# CampLet_Power_Control.net
KiCad netlist of a schematic drawn in EAGLE
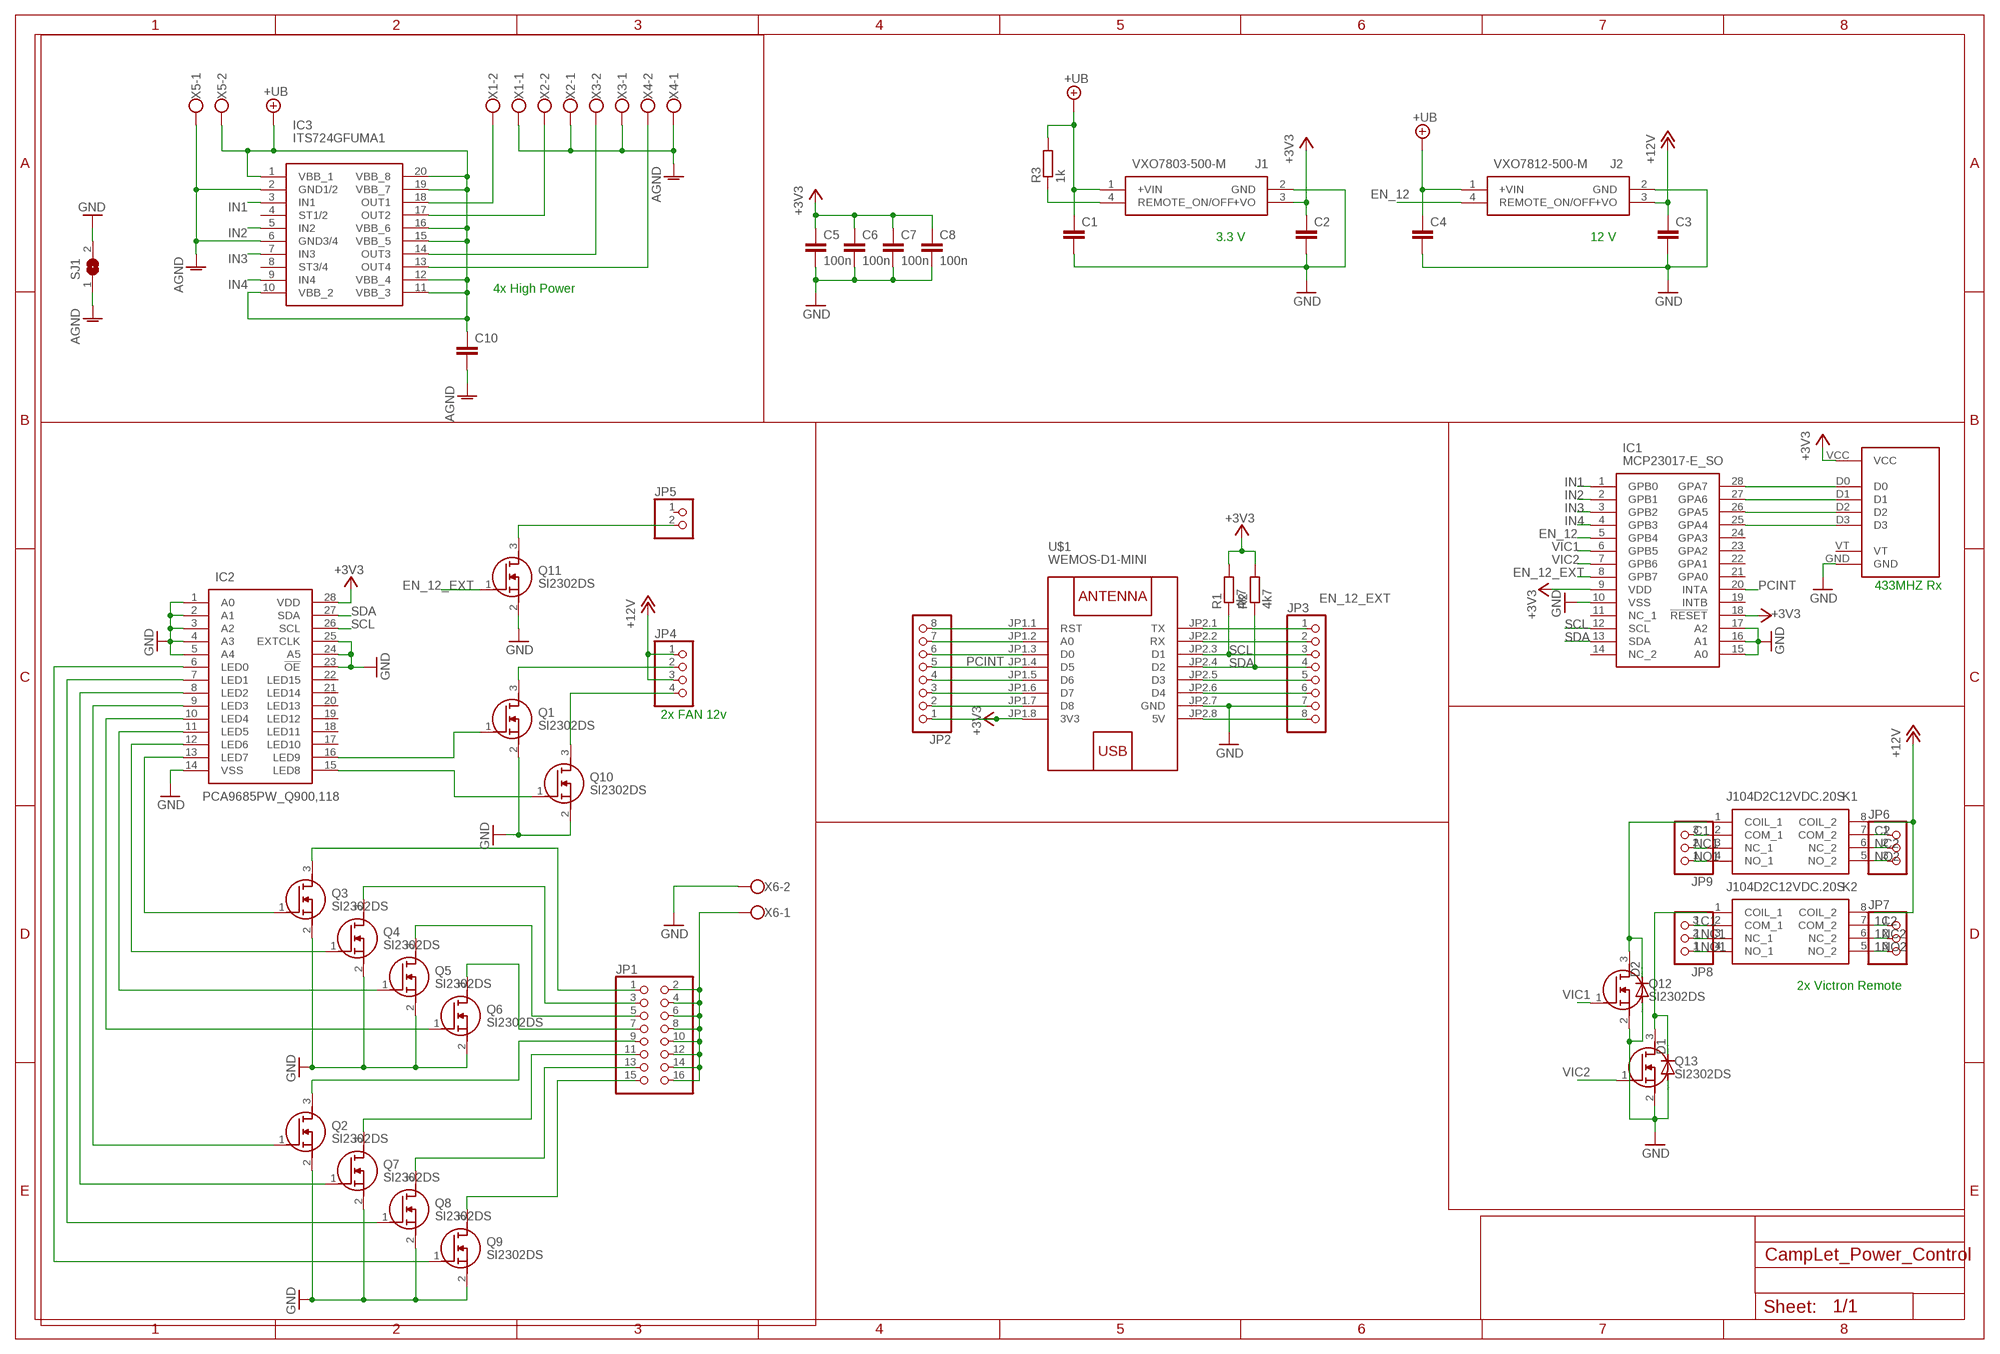
[diagram p0: schematic, sheet 1]

(export (version "E")
  (design (tool "Eeschema 10.0.6"))
  (components
    (comp (ref "C1")
      (value "10u 30v CL31A106KBHNNNE")
      (footprint "eagle-import:C1206")
      (libsource (lib "eagle-import") (part "C-EUC1206"))
    )
    (comp (ref "C2")
      (value "22u 3.3v CL31A226MOCLNNC")
      (footprint "eagle-import:C1206")
      (libsource (lib "eagle-import") (part "C-EUC1206"))
    )
    (comp (ref "C3")
      (value "22u 12v CL31A226MOCLNNC")
      (footprint "eagle-import:C1206")
      (libsource (lib "eagle-import") (part "C-EUC1206"))
    )
    (comp (ref "C4")
      (value "10u 30v CL31A106KBHNNNE")
      (footprint "eagle-import:C1206")
      (libsource (lib "eagle-import") (part "C-EUC1206"))
    )
    (comp (ref "C5")
      (value "100n")
      (footprint "eagle-import:C0805")
      (libsource (lib "eagle-import") (part "C-EUC0805"))
    )
    (comp (ref "C6")
      (value "100n")
      (footprint "eagle-import:C0805")
      (libsource (lib "eagle-import") (part "C-EUC0805"))
    )
    (comp (ref "C7")
      (value "100n")
      (footprint "eagle-import:C0805")
      (libsource (lib "eagle-import") (part "C-EUC0805"))
    )
    (comp (ref "C8")
      (value "100n")
      (footprint "eagle-import:C0805")
      (libsource (lib "eagle-import") (part "C-EUC0805"))
    )
    (comp (ref "C10")
      (value "10u 30v CL31A106KBHNNNE")
      (footprint "eagle-import:C1206")
      (libsource (lib "eagle-import") (part "C-EUC1206"))
    )
    (comp (ref "D1")
      (value "1N4148DO35-7")
      (footprint "eagle-import:DO35-7")
      (libsource (lib "eagle-import") (part "1N4148DO35-7"))
    )
    (comp (ref "D2")
      (value "1N4148DO35-7")
      (footprint "eagle-import:DO35-7")
      (libsource (lib "eagle-import") (part "1N4148DO35-7"))
    )
    (comp (ref "IC1")
      (value "MCP23017-E_SO")
      (footprint "eagle-import:SOIC127P1030X265-28N")
      (fields
        (field (name "ARROW_PART_NUMBER") "MCP23017-E/SO")
        (field (name "MOUSER_PART_NUMBER") "579-MCP23017-E/SO")
      )
      (libsource (lib "eagle-import") (part "MCP23017-E_SO"))
    )
    (comp (ref "IC2")
      (value "PCA9685PW_Q900,118")
      (footprint "eagle-import:SOP65P640X110-28N")
      (fields
        (field (name "ARROW_PART_NUMBER") "PCA9685PW/Q900,118")
        (field (name "MOUSER_PART_NUMBER") "771-PCA9685PWQ900118")
      )
      (libsource (lib "eagle-import") (part "PCA9685PW_Q900,118"))
    )
    (comp (ref "IC3")
      (value "ITS724GFUMA1")
      (footprint "eagle-import:SOIC127P1030X265-20N")
      (fields (field (name "MOUSER_PART_NUMBER") "726-ITS724GFUMA1"))
      (libsource (lib "eagle-import") (part "ITS724GFUMA1"))
    )
    (comp (ref "J1")
      (value "VXO7803-500-M")
      (footprint "eagle-import:VXO7803500MTR")
      (fields
        (field (name "ARROW_PART_NUMBER") "VXO7803-500-M-TR")
        (field (name "MOUSER_PART_NUMBER") "490-VXO7803-500-M-TR")
      )
      (libsource (lib "eagle-import") (part "VXO7803-500-M-TR"))
    )
    (comp (ref "J2")
      (value "VXO7812-500-M")
      (footprint "eagle-import:VXO7803500MTR")
      (fields
        (field (name "ARROW_PART_NUMBER") "VXO7803-500-M-TR")
        (field (name "MOUSER_PART_NUMBER") "490-VXO7803-500-M-TR")
      )
      (libsource (lib "eagle-import") (part "VXO7803-500-M-TR"))
    )
    (comp (ref "JP1")
      (value "PINHD-2X8")
      (footprint "eagle-import:2X08")
      (libsource (lib "eagle-import") (part "PINHD-2X8"))
    )
    (comp (ref "JP2")
      (value "PINHD-1X8")
      (footprint "eagle-import:1X08")
      (libsource (lib "eagle-import") (part "PINHD-1X8"))
    )
    (comp (ref "JP3")
      (value "PINHD-1X8")
      (footprint "eagle-import:1X08")
      (libsource (lib "eagle-import") (part "PINHD-1X8"))
    )
    (comp (ref "JP4")
      (value "PINHD-1X4")
      (footprint "eagle-import:1X04")
      (libsource (lib "eagle-import") (part "PINHD-1X4"))
    )
    (comp (ref "JP5")
      (value "PINHD-1X2")
      (footprint "eagle-import:1X02")
      (libsource (lib "eagle-import") (part "PINHD-1X2"))
    )
    (comp (ref "JP6")
      (value "PINHD-1X3")
      (footprint "eagle-import:1X03")
      (libsource (lib "eagle-import") (part "PINHD-1X3"))
    )
    (comp (ref "JP7")
      (value "PINHD-1X3")
      (footprint "eagle-import:1X03")
      (libsource (lib "eagle-import") (part "PINHD-1X3"))
    )
    (comp (ref "JP8")
      (value "PINHD-1X3")
      (footprint "eagle-import:1X03")
      (libsource (lib "eagle-import") (part "PINHD-1X3"))
    )
    (comp (ref "JP9")
      (value "PINHD-1X3")
      (footprint "eagle-import:1X03")
      (libsource (lib "eagle-import") (part "PINHD-1X3"))
    )
    (comp (ref "K1")
      (value "J104D2C12VDC.20S")
      (footprint "eagle-import:J104D2C12VDC20S")
      (libsource (lib "eagle-import") (part "J104D2C12VDC.20S"))
    )
    (comp (ref "K2")
      (value "J104D2C12VDC.20S")
      (footprint "eagle-import:J104D2C12VDC20S")
      (libsource (lib "eagle-import") (part "J104D2C12VDC.20S"))
    )
    (comp (ref "Q1")
      (value "SI2302DS")
      (footprint "eagle-import:SOT95P230X110-3N")
      (libsource (lib "eagle-import") (part "SI2302DS"))
    )
    (comp (ref "Q2")
      (value "SI2302DS")
      (footprint "eagle-import:SOT95P230X110-3N")
      (libsource (lib "eagle-import") (part "SI2302DS"))
    )
    (comp (ref "Q3")
      (value "SI2302DS")
      (footprint "eagle-import:SOT95P230X110-3N")
      (libsource (lib "eagle-import") (part "SI2302DS"))
    )
    (comp (ref "Q4")
      (value "SI2302DS")
      (footprint "eagle-import:SOT95P230X110-3N")
      (libsource (lib "eagle-import") (part "SI2302DS"))
    )
    (comp (ref "Q5")
      (value "SI2302DS")
      (footprint "eagle-import:SOT95P230X110-3N")
      (libsource (lib "eagle-import") (part "SI2302DS"))
    )
    (comp (ref "Q6")
      (value "SI2302DS")
      (footprint "eagle-import:SOT95P230X110-3N")
      (libsource (lib "eagle-import") (part "SI2302DS"))
    )
    (comp (ref "Q7")
      (value "SI2302DS")
      (footprint "eagle-import:SOT95P230X110-3N")
      (libsource (lib "eagle-import") (part "SI2302DS"))
    )
    (comp (ref "Q8")
      (value "SI2302DS")
      (footprint "eagle-import:SOT95P230X110-3N")
      (libsource (lib "eagle-import") (part "SI2302DS"))
    )
    (comp (ref "Q9")
      (value "SI2302DS")
      (footprint "eagle-import:SOT95P230X110-3N")
      (libsource (lib "eagle-import") (part "SI2302DS"))
    )
    (comp (ref "Q10")
      (value "SI2302DS")
      (footprint "eagle-import:SOT95P230X110-3N")
      (libsource (lib "eagle-import") (part "SI2302DS"))
    )
    (comp (ref "Q11")
      (value "SI2302DS")
      (footprint "eagle-import:SOT95P230X110-3N")
      (libsource (lib "eagle-import") (part "SI2302DS"))
    )
    (comp (ref "Q12")
      (value "SI2302DS")
      (footprint "eagle-import:SOT95P230X110-3N")
      (libsource (lib "eagle-import") (part "SI2302DS"))
    )
    (comp (ref "Q13")
      (value "SI2302DS")
      (footprint "eagle-import:SOT95P230X110-3N")
      (libsource (lib "eagle-import") (part "SI2302DS"))
    )
    (comp (ref "R1")
      (value "4k7")
      (footprint "eagle-import:R0805")
      (libsource (lib "eagle-import") (part "R-EU_R0805"))
    )
    (comp (ref "R2")
      (value "4k7")
      (footprint "eagle-import:R0805")
      (libsource (lib "eagle-import") (part "R-EU_R0805"))
    )
    (comp (ref "R3")
      (value "1k")
      (footprint "eagle-import:R0805")
      (libsource (lib "eagle-import") (part "R-EU_R0805"))
    )
    (comp (ref "SJ1") (value "SJ") (footprint "eagle-import:SJ") (libsource (lib "eagle-import") (part "SJ")))
    (comp (ref "U$1")
      (value "WEMOS-D1-MINI")
      (footprint "eagle-import:WEMOS-D1-MINI")
      (libsource (lib "eagle-import") (part "WEMOS-D1-MINI"))
    )
    (comp (ref "U$2")
      (value "433MHZ")
      (footprint "eagle-import:433MHZ")
      (libsource (lib "eagle-import") (part "433MHZ"))
    )
    (comp (ref "X1")
      (value "W237-102")
      (footprint "eagle-import:W237-102")
      (fields (field (name "MPN") "237-102"))
      (libsource (lib "eagle-import") (part "W237-102"))
    )
    (comp (ref "X2")
      (value "W237-102")
      (footprint "eagle-import:W237-102")
      (fields (field (name "MPN") "237-102"))
      (libsource (lib "eagle-import") (part "W237-102"))
    )
    (comp (ref "X3")
      (value "W237-102")
      (footprint "eagle-import:W237-102")
      (fields (field (name "MPN") "237-102"))
      (libsource (lib "eagle-import") (part "W237-102"))
    )
    (comp (ref "X4")
      (value "W237-102")
      (footprint "eagle-import:W237-102")
      (fields (field (name "MPN") "237-102"))
      (libsource (lib "eagle-import") (part "W237-102"))
    )
    (comp (ref "X5")
      (value "W237-102")
      (footprint "eagle-import:W237-102")
      (fields (field (name "MPN") "237-102"))
      (libsource (lib "eagle-import") (part "W237-102"))
    )
    (comp (ref "X6")
      (value "W237-102")
      (footprint "eagle-import:W237-102")
      (fields (field (name "MPN") "237-102"))
      (libsource (lib "eagle-import") (part "W237-102"))
    )
  )
  (nets
    (net (code "1") (name "+3V3") (class "Default")
      (node (ref "C2") (pin "1") (pinfunction "1_1") (pintype "passive"))
      (node (ref "C5") (pin "1") (pinfunction "1_1") (pintype "passive"))
      (node (ref "C6") (pin "1") (pinfunction "1_1") (pintype "passive"))
      (node (ref "C7") (pin "1") (pinfunction "1_1") (pintype "passive"))
      (node (ref "C8") (pin "1") (pinfunction "1_1") (pintype "passive"))
      (node (ref "IC1") (pin "18") (pinfunction "~{RESET}_18") (pintype "bidirectional"))
      (node (ref "IC1") (pin "9") (pinfunction "VDD_9") (pintype "bidirectional"))
      (node (ref "IC2") (pin "28") (pinfunction "VDD_28") (pintype "bidirectional"))
      (node (ref "J1") (pin "3") (pinfunction "+VO_3") (pintype "bidirectional"))
      (node (ref "JP2") (pin "1") (pinfunction "1_1") (pintype "passive"))
      (node (ref "R1") (pin "2") (pinfunction "2_2") (pintype "passive"))
      (node (ref "R2") (pin "2") (pinfunction "2_2") (pintype "passive"))
      (node (ref "U$1") (pin "JP1.8") (pinfunction "3V3_JP1.8") (pintype "power_in"))
      (node (ref "U$2") (pin "VCC") (pinfunction "VCC_VCC") (pintype "bidirectional"))
    )
    (net (code "2") (name "+12V") (class "Default")
      (node (ref "C3") (pin "1") (pinfunction "1_1") (pintype "passive"))
      (node (ref "J2") (pin "3") (pinfunction "+VO_3") (pintype "bidirectional"))
      (node (ref "JP4") (pin "1") (pinfunction "1_1") (pintype "passive"))
      (node (ref "JP4") (pin "3") (pinfunction "3_3") (pintype "passive"))
      (node (ref "K1") (pin "8") (pinfunction "COIL_2_8") (pintype "bidirectional"))
      (node (ref "K2") (pin "8") (pinfunction "COIL_2_8") (pintype "bidirectional"))
    )
    (net (code "3") (name "+UB") (class "Default")
      (node (ref "C1") (pin "1") (pinfunction "1_1") (pintype "passive"))
      (node (ref "C10") (pin "1") (pinfunction "1_1") (pintype "passive"))
      (node (ref "C4") (pin "1") (pinfunction "1_1") (pintype "passive"))
      (node (ref "IC3") (pin "1") (pinfunction "VBB_1_1") (pintype "bidirectional"))
      (node (ref "IC3") (pin "10") (pinfunction "VBB_2_10") (pintype "bidirectional"))
      (node (ref "IC3") (pin "11") (pinfunction "VBB_3_11") (pintype "bidirectional"))
      (node (ref "IC3") (pin "12") (pinfunction "VBB_4_12") (pintype "bidirectional"))
      (node (ref "IC3") (pin "15") (pinfunction "VBB_5_15") (pintype "bidirectional"))
      (node (ref "IC3") (pin "16") (pinfunction "VBB_6_16") (pintype "bidirectional"))
      (node (ref "IC3") (pin "19") (pinfunction "VBB_7_19") (pintype "bidirectional"))
      (node (ref "IC3") (pin "20") (pinfunction "VBB_8_20") (pintype "bidirectional"))
      (node (ref "J1") (pin "1") (pinfunction "+VIN_1") (pintype "bidirectional"))
      (node (ref "J2") (pin "1") (pinfunction "+VIN_1") (pintype "bidirectional"))
      (node (ref "R3") (pin "2") (pinfunction "2_2") (pintype "passive"))
      (node (ref "X5") (pin "2") (pinfunction "KL_2") (pintype "passive"))
    )
    (net (code "4") (name "/1C1") (class "Default")
      (node (ref "JP8") (pin "3") (pinfunction "3_3") (pintype "passive"))
      (node (ref "K2") (pin "2") (pinfunction "COM_1_2") (pintype "bidirectional"))
    )
    (net (code "5") (name "/1C2") (class "Default")
      (node (ref "JP7") (pin "1") (pinfunction "1_1") (pintype "passive"))
      (node (ref "K2") (pin "7") (pinfunction "COM_2_7") (pintype "bidirectional"))
    )
    (net (code "6") (name "/1NC1") (class "Default")
      (node (ref "JP8") (pin "2") (pinfunction "2_2") (pintype "passive"))
      (node (ref "K2") (pin "3") (pinfunction "NC_1_3") (pintype "bidirectional"))
    )
    (net (code "7") (name "/1NC2") (class "Default")
      (node (ref "JP7") (pin "2") (pinfunction "2_2") (pintype "passive"))
      (node (ref "K2") (pin "6") (pinfunction "NC_2_6") (pintype "bidirectional"))
    )
    (net (code "8") (name "/1NO1") (class "Default")
      (node (ref "JP8") (pin "1") (pinfunction "1_1") (pintype "passive"))
      (node (ref "K2") (pin "4") (pinfunction "NO_1_4") (pintype "bidirectional"))
    )
    (net (code "9") (name "/1NO2") (class "Default")
      (node (ref "JP7") (pin "3") (pinfunction "3_3") (pintype "passive"))
      (node (ref "K2") (pin "5") (pinfunction "NO_2_5") (pintype "bidirectional"))
    )
    (net (code "10") (name "/C1") (class "Default")
      (node (ref "JP9") (pin "3") (pinfunction "3_3") (pintype "passive"))
      (node (ref "K1") (pin "2") (pinfunction "COM_1_2") (pintype "bidirectional"))
    )
    (net (code "11") (name "/C2") (class "Default")
      (node (ref "JP6") (pin "1") (pinfunction "1_1") (pintype "passive"))
      (node (ref "K1") (pin "7") (pinfunction "COM_2_7") (pintype "bidirectional"))
    )
    (net (code "12") (name "/EN_12") (class "Default")
      (node (ref "IC1") (pin "5") (pinfunction "GPB4_5") (pintype "bidirectional"))
      (node (ref "J2") (pin "4") (pinfunction "REMOTE_ON/OFF_4") (pintype "bidirectional"))
    )
    (net (code "13") (name "/EN_12_EXT") (class "Default")
      (node (ref "IC1") (pin "8") (pinfunction "GPB7_8") (pintype "bidirectional"))
      (node (ref "Q11") (pin "1") (pinfunction "G_1") (pintype "bidirectional"))
    )
    (net (code "14") (name "/IN1") (class "Default")
      (node (ref "IC1") (pin "1") (pinfunction "GPB0_1") (pintype "bidirectional"))
      (node (ref "IC3") (pin "3") (pinfunction "IN1_3") (pintype "bidirectional"))
    )
    (net (code "15") (name "/IN2") (class "Default")
      (node (ref "IC1") (pin "2") (pinfunction "GPB1_2") (pintype "bidirectional"))
      (node (ref "IC3") (pin "5") (pinfunction "IN2_5") (pintype "bidirectional"))
    )
    (net (code "16") (name "/IN3") (class "Default")
      (node (ref "IC1") (pin "3") (pinfunction "GPB2_3") (pintype "bidirectional"))
      (node (ref "IC3") (pin "7") (pinfunction "IN3_7") (pintype "bidirectional"))
    )
    (net (code "17") (name "/IN4") (class "Default")
      (node (ref "IC1") (pin "4") (pinfunction "GPB3_4") (pintype "bidirectional"))
      (node (ref "IC3") (pin "9") (pinfunction "IN4_9") (pintype "bidirectional"))
    )
    (net (code "18") (name "/NC1") (class "Default")
      (node (ref "JP9") (pin "2") (pinfunction "2_2") (pintype "passive"))
      (node (ref "K1") (pin "3") (pinfunction "NC_1_3") (pintype "bidirectional"))
    )
    (net (code "19") (name "/NC2") (class "Default")
      (node (ref "JP6") (pin "2") (pinfunction "2_2") (pintype "passive"))
      (node (ref "K1") (pin "6") (pinfunction "NC_2_6") (pintype "bidirectional"))
    )
    (net (code "20") (name "/NO1") (class "Default")
      (node (ref "JP9") (pin "1") (pinfunction "1_1") (pintype "passive"))
      (node (ref "K1") (pin "4") (pinfunction "NO_1_4") (pintype "bidirectional"))
    )
    (net (code "21") (name "/NO2") (class "Default")
      (node (ref "JP6") (pin "3") (pinfunction "3_3") (pintype "passive"))
      (node (ref "K1") (pin "5") (pinfunction "NO_2_5") (pintype "bidirectional"))
    )
    (net (code "22") (name "/PCINT") (class "Default")
      (node (ref "IC1") (pin "20") (pinfunction "INTA_20") (pintype "bidirectional"))
      (node (ref "JP2") (pin "5") (pinfunction "5_5") (pintype "passive"))
      (node (ref "U$1") (pin "JP1.4") (pinfunction "D5_JP1.4") (pintype "bidirectional"))
    )
    (net (code "23") (name "/SCL") (class "Default")
      (node (ref "IC1") (pin "12") (pinfunction "SCL_12") (pintype "bidirectional"))
      (node (ref "IC2") (pin "26") (pinfunction "SCL_26") (pintype "bidirectional"))
      (node (ref "JP3") (pin "3") (pinfunction "3_3") (pintype "passive"))
      (node (ref "R1") (pin "1") (pinfunction "1_1") (pintype "passive"))
      (node (ref "U$1") (pin "JP2.3") (pinfunction "D1_JP2.3") (pintype "bidirectional"))
    )
    (net (code "24") (name "/SDA") (class "Default")
      (node (ref "IC1") (pin "13") (pinfunction "SDA_13") (pintype "bidirectional"))
      (node (ref "IC2") (pin "27") (pinfunction "SDA_27") (pintype "bidirectional"))
      (node (ref "JP3") (pin "4") (pinfunction "4_4") (pintype "passive"))
      (node (ref "R2") (pin "1") (pinfunction "1_1") (pintype "passive"))
      (node (ref "U$1") (pin "JP2.4") (pinfunction "D2_JP2.4") (pintype "bidirectional"))
    )
    (net (code "25") (name "/VIC1") (class "Default")
      (node (ref "IC1") (pin "6") (pinfunction "GPB5_6") (pintype "bidirectional"))
      (node (ref "Q12") (pin "1") (pinfunction "G_1") (pintype "bidirectional"))
    )
    (net (code "26") (name "/VIC2") (class "Default")
      (node (ref "IC1") (pin "7") (pinfunction "GPB6_7") (pintype "bidirectional"))
      (node (ref "Q13") (pin "1") (pinfunction "G_1") (pintype "bidirectional"))
    )
    (net (code "27") (name "AGND") (class "Default")
      (node (ref "C10") (pin "2") (pinfunction "2_2") (pintype "passive"))
      (node (ref "IC3") (pin "2") (pinfunction "GND1/2_2") (pintype "bidirectional"))
      (node (ref "IC3") (pin "6") (pinfunction "GND3/4_6") (pintype "bidirectional"))
      (node (ref "SJ1") (pin "1") (pinfunction "1_1") (pintype "passive"))
      (node (ref "X1") (pin "1") (pinfunction "KL_1") (pintype "passive"))
      (node (ref "X2") (pin "1") (pinfunction "KL_1") (pintype "passive"))
      (node (ref "X3") (pin "1") (pinfunction "KL_1") (pintype "passive"))
      (node (ref "X4") (pin "1") (pinfunction "KL_1") (pintype "passive"))
      (node (ref "X5") (pin "1") (pinfunction "KL_1") (pintype "passive"))
    )
    (net (code "28") (name "GND") (class "Default")
      (node (ref "C1") (pin "2") (pinfunction "2_2") (pintype "passive"))
      (node (ref "C2") (pin "2") (pinfunction "2_2") (pintype "passive"))
      (node (ref "C3") (pin "2") (pinfunction "2_2") (pintype "passive"))
      (node (ref "C4") (pin "2") (pinfunction "2_2") (pintype "passive"))
      (node (ref "C5") (pin "2") (pinfunction "2_2") (pintype "passive"))
      (node (ref "C6") (pin "2") (pinfunction "2_2") (pintype "passive"))
      (node (ref "C7") (pin "2") (pinfunction "2_2") (pintype "passive"))
      (node (ref "C8") (pin "2") (pinfunction "2_2") (pintype "passive"))
      (node (ref "D1") (pin "A") (pinfunction "A_A") (pintype "passive"))
      (node (ref "D2") (pin "A") (pinfunction "A_A") (pintype "passive"))
      (node (ref "IC1") (pin "10") (pinfunction "VSS_10") (pintype "bidirectional"))
      (node (ref "IC1") (pin "15") (pinfunction "A0_15") (pintype "bidirectional"))
      (node (ref "IC1") (pin "16") (pinfunction "A1_16") (pintype "bidirectional"))
      (node (ref "IC1") (pin "17") (pinfunction "A2_17") (pintype "bidirectional"))
      (node (ref "IC2") (pin "1") (pinfunction "A0_1") (pintype "bidirectional"))
      (node (ref "IC2") (pin "14") (pinfunction "VSS_14") (pintype "bidirectional"))
      (node (ref "IC2") (pin "2") (pinfunction "A1_2") (pintype "bidirectional"))
      (node (ref "IC2") (pin "23") (pinfunction "~{OE}_23") (pintype "bidirectional"))
      (node (ref "IC2") (pin "24") (pinfunction "A5_24") (pintype "bidirectional"))
      (node (ref "IC2") (pin "25") (pinfunction "EXTCLK_25") (pintype "bidirectional"))
      (node (ref "IC2") (pin "3") (pinfunction "A2_3") (pintype "bidirectional"))
      (node (ref "IC2") (pin "4") (pinfunction "A3_4") (pintype "bidirectional"))
      (node (ref "IC2") (pin "5") (pinfunction "A4_5") (pintype "bidirectional"))
      (node (ref "J1") (pin "2") (pinfunction "GND_2") (pintype "bidirectional"))
      (node (ref "J2") (pin "2") (pinfunction "GND_2") (pintype "bidirectional"))
      (node (ref "JP3") (pin "7") (pinfunction "7_7") (pintype "passive"))
      (node (ref "Q1") (pin "2") (pinfunction "S_2") (pintype "bidirectional"))
      (node (ref "Q10") (pin "2") (pinfunction "S_2") (pintype "bidirectional"))
      (node (ref "Q11") (pin "2") (pinfunction "S_2") (pintype "bidirectional"))
      (node (ref "Q12") (pin "2") (pinfunction "S_2") (pintype "bidirectional"))
      (node (ref "Q13") (pin "2") (pinfunction "S_2") (pintype "bidirectional"))
      (node (ref "Q2") (pin "2") (pinfunction "S_2") (pintype "bidirectional"))
      (node (ref "Q3") (pin "2") (pinfunction "S_2") (pintype "bidirectional"))
      (node (ref "Q4") (pin "2") (pinfunction "S_2") (pintype "bidirectional"))
      (node (ref "Q5") (pin "2") (pinfunction "S_2") (pintype "bidirectional"))
      (node (ref "Q6") (pin "2") (pinfunction "S_2") (pintype "bidirectional"))
      (node (ref "Q7") (pin "2") (pinfunction "S_2") (pintype "bidirectional"))
      (node (ref "Q8") (pin "2") (pinfunction "S_2") (pintype "bidirectional"))
      (node (ref "Q9") (pin "2") (pinfunction "S_2") (pintype "bidirectional"))
      (node (ref "SJ1") (pin "2") (pinfunction "2_2") (pintype "passive"))
      (node (ref "U$1") (pin "JP2.7") (pinfunction "GND_JP2.7") (pintype "power_in"))
      (node (ref "U$2") (pin "GND") (pinfunction "GND_GND") (pintype "bidirectional"))
      (node (ref "X6") (pin "2") (pinfunction "KL_2") (pintype "passive"))
    )
    (net (code "29") (name "Net-(IC1-GPA4)") (class "Default")
      (node (ref "IC1") (pin "25") (pinfunction "GPA4_25") (pintype "bidirectional"))
      (node (ref "U$2") (pin "D3") (pinfunction "D3_D3") (pintype "bidirectional"))
    )
    (net (code "30") (name "Net-(IC1-GPA5)") (class "Default")
      (node (ref "IC1") (pin "26") (pinfunction "GPA5_26") (pintype "bidirectional"))
      (node (ref "U$2") (pin "D2") (pinfunction "D2_D2") (pintype "bidirectional"))
    )
    (net (code "31") (name "Net-(IC1-GPA6)") (class "Default")
      (node (ref "IC1") (pin "27") (pinfunction "GPA6_27") (pintype "bidirectional"))
      (node (ref "U$2") (pin "D1") (pinfunction "D1_D1") (pintype "bidirectional"))
    )
    (net (code "32") (name "Net-(IC1-GPA7)") (class "Default")
      (node (ref "IC1") (pin "28") (pinfunction "GPA7_28") (pintype "bidirectional"))
      (node (ref "U$2") (pin "D0") (pinfunction "D0_D0") (pintype "bidirectional"))
    )
    (net (code "33") (name "Net-(IC2-LED0)") (class "Default")
      (node (ref "IC2") (pin "6") (pinfunction "LED0_6") (pintype "bidirectional"))
      (node (ref "Q9") (pin "1") (pinfunction "G_1") (pintype "bidirectional"))
    )
    (net (code "34") (name "Net-(IC2-LED1)") (class "Default")
      (node (ref "IC2") (pin "7") (pinfunction "LED1_7") (pintype "bidirectional"))
      (node (ref "Q8") (pin "1") (pinfunction "G_1") (pintype "bidirectional"))
    )
    (net (code "35") (name "Net-(IC2-LED2)") (class "Default")
      (node (ref "IC2") (pin "8") (pinfunction "LED2_8") (pintype "bidirectional"))
      (node (ref "Q7") (pin "1") (pinfunction "G_1") (pintype "bidirectional"))
    )
    (net (code "36") (name "Net-(IC2-LED3)") (class "Default")
      (node (ref "IC2") (pin "9") (pinfunction "LED3_9") (pintype "bidirectional"))
      (node (ref "Q2") (pin "1") (pinfunction "G_1") (pintype "bidirectional"))
    )
    (net (code "37") (name "Net-(IC2-LED4)") (class "Default")
      (node (ref "IC2") (pin "10") (pinfunction "LED4_10") (pintype "bidirectional"))
      (node (ref "Q6") (pin "1") (pinfunction "G_1") (pintype "bidirectional"))
    )
    (net (code "38") (name "Net-(IC2-LED5)") (class "Default")
      (node (ref "IC2") (pin "11") (pinfunction "LED5_11") (pintype "bidirectional"))
      (node (ref "Q5") (pin "1") (pinfunction "G_1") (pintype "bidirectional"))
    )
    (net (code "39") (name "Net-(IC2-LED6)") (class "Default")
      (node (ref "IC2") (pin "12") (pinfunction "LED6_12") (pintype "bidirectional"))
      (node (ref "Q4") (pin "1") (pinfunction "G_1") (pintype "bidirectional"))
    )
    (net (code "40") (name "Net-(IC2-LED7)") (class "Default")
      (node (ref "IC2") (pin "13") (pinfunction "LED7_13") (pintype "bidirectional"))
      (node (ref "Q3") (pin "1") (pinfunction "G_1") (pintype "bidirectional"))
    )
    (net (code "41") (name "Net-(IC2-LED8)") (class "Default")
      (node (ref "IC2") (pin "15") (pinfunction "LED8_15") (pintype "bidirectional"))
      (node (ref "Q10") (pin "1") (pinfunction "G_1") (pintype "bidirectional"))
    )
    (net (code "42") (name "Net-(IC2-LED9)") (class "Default")
      (node (ref "IC2") (pin "16") (pinfunction "LED9_16") (pintype "bidirectional"))
      (node (ref "Q1") (pin "1") (pinfunction "G_1") (pintype "bidirectional"))
    )
    (net (code "43") (name "Net-(IC3-OUT1)") (class "Default")
      (node (ref "IC3") (pin "18") (pinfunction "OUT1_18") (pintype "bidirectional"))
      (node (ref "X1") (pin "2") (pinfunction "KL_2") (pintype "passive"))
    )
    (net (code "44") (name "Net-(IC3-OUT2)") (class "Default")
      (node (ref "IC3") (pin "17") (pinfunction "OUT2_17") (pintype "bidirectional"))
      (node (ref "X2") (pin "2") (pinfunction "KL_2") (pintype "passive"))
    )
    (net (code "45") (name "Net-(IC3-OUT3)") (class "Default")
      (node (ref "IC3") (pin "14") (pinfunction "OUT3_14") (pintype "bidirectional"))
      (node (ref "X3") (pin "2") (pinfunction "KL_2") (pintype "passive"))
    )
    (net (code "46") (name "Net-(IC3-OUT4)") (class "Default")
      (node (ref "IC3") (pin "13") (pinfunction "OUT4_13") (pintype "bidirectional"))
      (node (ref "X4") (pin "2") (pinfunction "KL_2") (pintype "passive"))
    )
    (net (code "47") (name "Net-(J1-REMOTE_ON{slash}OFF)") (class "Default")
      (node (ref "J1") (pin "4") (pinfunction "REMOTE_ON/OFF_4") (pintype "bidirectional"))
      (node (ref "R3") (pin "1") (pinfunction "1_1") (pintype "passive"))
    )
    (net (code "48") (name "Net-(K1-COIL_1)") (class "Default")
      (node (ref "D2") (pin "C") (pinfunction "C_C") (pintype "passive"))
      (node (ref "K1") (pin "1") (pinfunction "COIL_1_1") (pintype "bidirectional"))
      (node (ref "Q12") (pin "3") (pinfunction "D_3") (pintype "bidirectional"))
    )
    (net (code "49") (name "Net-(K2-COIL_1)") (class "Default")
      (node (ref "D1") (pin "C") (pinfunction "C_C") (pintype "passive"))
      (node (ref "K2") (pin "1") (pinfunction "COIL_1_1") (pintype "bidirectional"))
      (node (ref "Q13") (pin "3") (pinfunction "D_3") (pintype "bidirectional"))
    )
    (net (code "50") (name "Net-(Q1-D)") (class "Default")
      (node (ref "JP4") (pin "2") (pinfunction "2_2") (pintype "passive"))
      (node (ref "Q1") (pin "3") (pinfunction "D_3") (pintype "bidirectional"))
    )
    (net (code "51") (name "Net-(Q2-D)") (class "Default")
      (node (ref "JP1") (pin "9") (pinfunction "9_9") (pintype "passive"))
      (node (ref "Q2") (pin "3") (pinfunction "D_3") (pintype "bidirectional"))
    )
    (net (code "52") (name "Net-(Q3-D)") (class "Default")
      (node (ref "JP1") (pin "1") (pinfunction "1_1") (pintype "passive"))
      (node (ref "Q3") (pin "3") (pinfunction "D_3") (pintype "bidirectional"))
    )
    (net (code "53") (name "Net-(Q4-D)") (class "Default")
      (node (ref "JP1") (pin "3") (pinfunction "3_3") (pintype "passive"))
      (node (ref "Q4") (pin "3") (pinfunction "D_3") (pintype "bidirectional"))
    )
    (net (code "54") (name "Net-(Q5-D)") (class "Default")
      (node (ref "JP1") (pin "5") (pinfunction "5_5") (pintype "passive"))
      (node (ref "Q5") (pin "3") (pinfunction "D_3") (pintype "bidirectional"))
    )
    (net (code "55") (name "Net-(Q6-D)") (class "Default")
      (node (ref "JP1") (pin "7") (pinfunction "7_7") (pintype "passive"))
      (node (ref "Q6") (pin "3") (pinfunction "D_3") (pintype "bidirectional"))
    )
    (net (code "56") (name "Net-(Q7-D)") (class "Default")
      (node (ref "JP1") (pin "11") (pinfunction "11_11") (pintype "passive"))
      (node (ref "Q7") (pin "3") (pinfunction "D_3") (pintype "bidirectional"))
    )
    (net (code "57") (name "Net-(Q8-D)") (class "Default")
      (node (ref "JP1") (pin "13") (pinfunction "13_13") (pintype "passive"))
      (node (ref "Q8") (pin "3") (pinfunction "D_3") (pintype "bidirectional"))
    )
    (net (code "58") (name "Net-(Q9-D)") (class "Default")
      (node (ref "JP1") (pin "15") (pinfunction "15_15") (pintype "passive"))
      (node (ref "Q9") (pin "3") (pinfunction "D_3") (pintype "bidirectional"))
    )
    (net (code "59") (name "Net-(Q10-D)") (class "Default")
      (node (ref "JP4") (pin "4") (pinfunction "4_4") (pintype "passive"))
      (node (ref "Q10") (pin "3") (pinfunction "D_3") (pintype "bidirectional"))
    )
    (net (code "60") (name "Net-(Q11-D)") (class "Default")
      (node (ref "JP5") (pin "2") (pinfunction "2_2") (pintype "passive"))
      (node (ref "Q11") (pin "3") (pinfunction "D_3") (pintype "bidirectional"))
    )
    (net (code "61") (name "Net-(U$1-5V)") (class "Default")
      (node (ref "JP3") (pin "8") (pinfunction "8_8") (pintype "passive"))
      (node (ref "U$1") (pin "JP2.8") (pinfunction "5V_JP2.8") (pintype "power_in"))
    )
    (net (code "62") (name "Net-(U$1-A0)") (class "Default")
      (node (ref "JP2") (pin "7") (pinfunction "7_7") (pintype "passive"))
      (node (ref "U$1") (pin "JP1.2") (pinfunction "A0_JP1.2") (pintype "bidirectional"))
    )
    (net (code "63") (name "Net-(U$1-D0)") (class "Default")
      (node (ref "JP2") (pin "6") (pinfunction "6_6") (pintype "passive"))
      (node (ref "U$1") (pin "JP1.3") (pinfunction "D0_JP1.3") (pintype "bidirectional"))
    )
    (net (code "64") (name "Net-(U$1-D3)") (class "Default")
      (node (ref "JP3") (pin "5") (pinfunction "5_5") (pintype "passive"))
      (node (ref "U$1") (pin "JP2.5") (pinfunction "D3_JP2.5") (pintype "bidirectional"))
    )
    (net (code "65") (name "Net-(U$1-D4)") (class "Default")
      (node (ref "JP3") (pin "6") (pinfunction "6_6") (pintype "passive"))
      (node (ref "U$1") (pin "JP2.6") (pinfunction "D4_JP2.6") (pintype "bidirectional"))
    )
    (net (code "66") (name "Net-(U$1-D6)") (class "Default")
      (node (ref "JP2") (pin "4") (pinfunction "4_4") (pintype "passive"))
      (node (ref "U$1") (pin "JP1.5") (pinfunction "D6_JP1.5") (pintype "bidirectional"))
    )
    (net (code "67") (name "Net-(U$1-D7)") (class "Default")
      (node (ref "JP2") (pin "3") (pinfunction "3_3") (pintype "passive"))
      (node (ref "U$1") (pin "JP1.6") (pinfunction "D7_JP1.6") (pintype "bidirectional"))
    )
    (net (code "68") (name "Net-(U$1-D8)") (class "Default")
      (node (ref "JP2") (pin "2") (pinfunction "2_2") (pintype "passive"))
      (node (ref "U$1") (pin "JP1.7") (pinfunction "D8_JP1.7") (pintype "bidirectional"))
    )
    (net (code "69") (name "Net-(U$1-RST)") (class "Default")
      (node (ref "JP2") (pin "8") (pinfunction "8_8") (pintype "passive"))
      (node (ref "U$1") (pin "JP1.1") (pinfunction "RST_JP1.1") (pintype "bidirectional"))
    )
    (net (code "70") (name "Net-(U$1-RX)") (class "Default")
      (node (ref "JP3") (pin "2") (pinfunction "2_2") (pintype "passive"))
      (node (ref "U$1") (pin "JP2.2") (pinfunction "RX_JP2.2") (pintype "bidirectional"))
    )
    (net (code "71") (name "Net-(U$1-TX)") (class "Default")
      (node (ref "JP3") (pin "1") (pinfunction "1_1") (pintype "passive"))
      (node (ref "U$1") (pin "JP2.1") (pinfunction "TX_JP2.1") (pintype "bidirectional"))
    )
    (net (code "72") (name "Net-(X6A-KL)") (class "Default")
      (node (ref "JP1") (pin "10") (pinfunction "10_10") (pintype "passive"))
      (node (ref "JP1") (pin "12") (pinfunction "12_12") (pintype "passive"))
      (node (ref "JP1") (pin "14") (pinfunction "14_14") (pintype "passive"))
      (node (ref "JP1") (pin "16") (pinfunction "16_16") (pintype "passive"))
      (node (ref "JP1") (pin "2") (pinfunction "2_2") (pintype "passive"))
      (node (ref "JP1") (pin "4") (pinfunction "4_4") (pintype "passive"))
      (node (ref "JP1") (pin "6") (pinfunction "6_6") (pintype "passive"))
      (node (ref "JP1") (pin "8") (pinfunction "8_8") (pintype "passive"))
      (node (ref "X6") (pin "1") (pinfunction "KL_1") (pintype "passive"))
    )
    (net (code "73") (name "unconnected-(IC1-GPA0-Pad21)") (class "Default")
      (node (ref "IC1") (pin "21") (pinfunction "GPA0_21") (pintype "bidirectional"))
    )
    (net (code "74") (name "unconnected-(IC1-GPA1-Pad22)") (class "Default")
      (node (ref "IC1") (pin "22") (pinfunction "GPA1_22") (pintype "bidirectional"))
    )
    (net (code "75") (name "unconnected-(IC1-GPA2-Pad23)") (class "Default")
      (node (ref "IC1") (pin "23") (pinfunction "GPA2_23") (pintype "bidirectional"))
    )
    (net (code "76") (name "unconnected-(IC1-GPA3-Pad24)") (class "Default")
      (node (ref "IC1") (pin "24") (pinfunction "GPA3_24") (pintype "bidirectional"))
    )
    (net (code "77") (name "unconnected-(IC1-INTB-Pad19)") (class "Default")
      (node (ref "IC1") (pin "19") (pinfunction "INTB_19") (pintype "bidirectional"))
    )
    (net (code "78") (name "unconnected-(IC1-NC_1-Pad11)") (class "Default")
      (node (ref "IC1") (pin "11") (pinfunction "NC_1_11") (pintype "bidirectional"))
    )
    (net (code "79") (name "unconnected-(IC1-NC_2-Pad14)") (class "Default")
      (node (ref "IC1") (pin "14") (pinfunction "NC_2_14") (pintype "bidirectional"))
    )
    (net (code "80") (name "unconnected-(IC2-LED10-Pad17)") (class "Default")
      (node (ref "IC2") (pin "17") (pinfunction "LED10_17") (pintype "bidirectional"))
    )
    (net (code "81") (name "unconnected-(IC2-LED11-Pad18)") (class "Default")
      (node (ref "IC2") (pin "18") (pinfunction "LED11_18") (pintype "bidirectional"))
    )
    (net (code "82") (name "unconnected-(IC2-LED12-Pad19)") (class "Default")
      (node (ref "IC2") (pin "19") (pinfunction "LED12_19") (pintype "bidirectional"))
    )
    (net (code "83") (name "unconnected-(IC2-LED13-Pad20)") (class "Default")
      (node (ref "IC2") (pin "20") (pinfunction "LED13_20") (pintype "bidirectional"))
    )
    (net (code "84") (name "unconnected-(IC2-LED14-Pad21)") (class "Default")
      (node (ref "IC2") (pin "21") (pinfunction "LED14_21") (pintype "bidirectional"))
    )
    (net (code "85") (name "unconnected-(IC2-LED15-Pad22)") (class "Default")
      (node (ref "IC2") (pin "22") (pinfunction "LED15_22") (pintype "bidirectional"))
    )
    (net (code "86") (name "unconnected-(IC3-ST1{slash}2-Pad4)") (class "Default")
      (node (ref "IC3") (pin "4") (pinfunction "ST1/2_4") (pintype "bidirectional"))
    )
    (net (code "87") (name "unconnected-(IC3-ST3{slash}4-Pad8)") (class "Default")
      (node (ref "IC3") (pin "8") (pinfunction "ST3/4_8") (pintype "bidirectional"))
    )
    (net (code "88") (name "unconnected-(JP5-Pad1)") (class "Default")
      (node (ref "JP5") (pin "1") (pinfunction "1_1") (pintype "passive"))
    )
    (net (code "89") (name "unconnected-(U$2-PadVT)") (class "Default")
      (node (ref "U$2") (pin "VT") (pinfunction "VT_VT") (pintype "bidirectional"))
    )
  )
)
